# stm_teensy.net
KiCad netlist of a schematic drawn in EAGLE
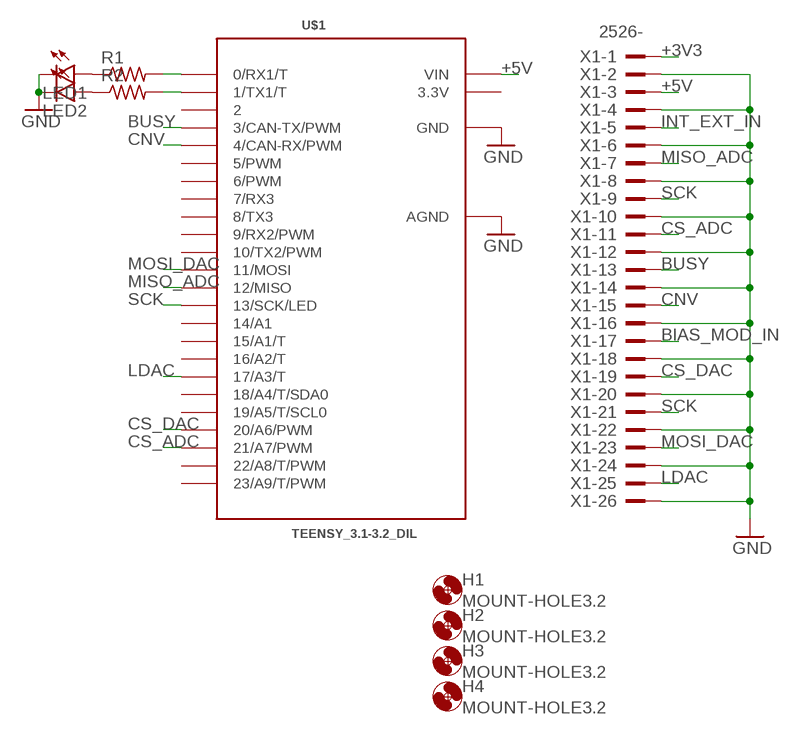
[diagram p0: schematic, sheet 1]

(export (version "E")
  (design (tool "Eeschema 10.0.6"))
  (components
    (comp (ref "H1")
      (value "MOUNT-HOLE3.2")
      (footprint "eagle-import:3,2")
      (libsource (lib "eagle-import") (part "MOUNT-HOLE3.2"))
    )
    (comp (ref "H2")
      (value "MOUNT-HOLE3.2")
      (footprint "eagle-import:3,2")
      (libsource (lib "eagle-import") (part "MOUNT-HOLE3.2"))
    )
    (comp (ref "H3")
      (value "MOUNT-HOLE3.2")
      (footprint "eagle-import:3,2")
      (libsource (lib "eagle-import") (part "MOUNT-HOLE3.2"))
    )
    (comp (ref "H4")
      (value "MOUNT-HOLE3.2")
      (footprint "eagle-import:3,2")
      (libsource (lib "eagle-import") (part "MOUNT-HOLE3.2"))
    )
    (comp (ref "LED1")
      (value "LED5MM")
      (footprint "eagle-import:LED5MM")
      (libsource (lib "eagle-import") (part "LED5MM"))
    )
    (comp (ref "LED2")
      (value "LED5MM")
      (footprint "eagle-import:LED5MM")
      (libsource (lib "eagle-import") (part "LED5MM"))
    )
    (comp (ref "R1")
      (value "R-US_0204/7")
      (footprint "eagle-import:0204_7")
      (libsource (lib "eagle-import") (part "R-US_0204/7"))
    )
    (comp (ref "R2")
      (value "R-US_0204/7")
      (footprint "eagle-import:0204_7")
      (libsource (lib "eagle-import") (part "R-US_0204/7"))
    )
    (comp (ref "U$1")
      (value "TEENSY_3.1-3.2_DIL")
      (footprint "eagle-import:TEENSY_3.0-3.2&LC_DIL")
      (libsource (lib "eagle-import") (part "TEENSY_3.1-3.2_DIL"))
    )
    (comp (ref "X1")
      (value "2526-")
      (footprint "eagle-import:PAK100_2500-26")
      (libsource (lib "eagle-import") (part "2526-"))
    )
  )
  (nets
    (net (code "1") (name "/+3V3") (class "Default")
      (node (ref "X1") (pin "1") (pinfunction "KL_1") (pintype "passive"))
    )
    (net (code "2") (name "/+5V") (class "Default")
      (node (ref "U$1") (pin "VIN") (pinfunction "VIN_VIN") (pintype "power_in"))
      (node (ref "X1") (pin "3") (pinfunction "KL_3") (pintype "passive"))
    )
    (net (code "3") (name "/3.3V") (class "Default")
      (node (ref "U$1") (pin "3.3V") (pinfunction "3.3V_3.3V") (pintype "power_in"))
    )
    (net (code "4") (name "/BIAS_MOD_IN") (class "Default")
      (node (ref "X1") (pin "17") (pinfunction "KL_17") (pintype "passive"))
    )
    (net (code "5") (name "/BUSY") (class "Default")
      (node (ref "U$1") (pin "3") (pinfunction "3/CAN-TX/PWM_3") (pintype "bidirectional"))
      (node (ref "X1") (pin "13") (pinfunction "KL_13") (pintype "passive"))
    )
    (net (code "6") (name "/CNV") (class "Default")
      (node (ref "U$1") (pin "4") (pinfunction "4/CAN-RX/PWM_4") (pintype "bidirectional"))
      (node (ref "X1") (pin "15") (pinfunction "KL_15") (pintype "passive"))
    )
    (net (code "7") (name "/CS_ADC") (class "Default")
      (node (ref "U$1") (pin "21/A7") (pinfunction "21/A7/PWM_21/A7") (pintype "bidirectional"))
      (node (ref "X1") (pin "11") (pinfunction "KL_11") (pintype "passive"))
    )
    (net (code "8") (name "/CS_DAC") (class "Default")
      (node (ref "U$1") (pin "20/A6") (pinfunction "20/A6/PWM_20/A6") (pintype "bidirectional"))
      (node (ref "X1") (pin "19") (pinfunction "KL_19") (pintype "passive"))
    )
    (net (code "9") (name "/INT_EXT_IN") (class "Default")
      (node (ref "X1") (pin "5") (pinfunction "KL_5") (pintype "passive"))
    )
    (net (code "10") (name "/LDAC") (class "Default")
      (node (ref "U$1") (pin "17/A3") (pinfunction "17/A3/T_17/A3") (pintype "bidirectional"))
      (node (ref "X1") (pin "25") (pinfunction "KL_25") (pintype "passive"))
    )
    (net (code "11") (name "/MISO_ADC") (class "Default")
      (node (ref "U$1") (pin "12") (pinfunction "12/MISO_12") (pintype "bidirectional"))
      (node (ref "X1") (pin "7") (pinfunction "KL_7") (pintype "passive"))
    )
    (net (code "12") (name "/MOSI_DAC") (class "Default")
      (node (ref "U$1") (pin "11") (pinfunction "11/MOSI_11") (pintype "bidirectional"))
      (node (ref "X1") (pin "23") (pinfunction "KL_23") (pintype "passive"))
    )
    (net (code "13") (name "/SCK") (class "Default")
      (node (ref "U$1") (pin "13") (pinfunction "13/SCK/LED_13") (pintype "bidirectional"))
      (node (ref "X1") (pin "21") (pinfunction "KL_21") (pintype "passive"))
      (node (ref "X1") (pin "9") (pinfunction "KL_9") (pintype "passive"))
    )
    (net (code "14") (name "GND") (class "Default")
      (node (ref "LED1") (pin "K") (pinfunction "C_K") (pintype "passive"))
      (node (ref "LED2") (pin "K") (pinfunction "C_K") (pintype "passive"))
      (node (ref "U$1") (pin "AGND") (pinfunction "AGND_AGND") (pintype "power_in"))
      (node (ref "U$1") (pin "GND") (pinfunction "GND_GND") (pintype "power_in"))
      (node (ref "X1") (pin "10") (pinfunction "KL_10") (pintype "passive"))
      (node (ref "X1") (pin "12") (pinfunction "KL_12") (pintype "passive"))
      (node (ref "X1") (pin "14") (pinfunction "KL_14") (pintype "passive"))
      (node (ref "X1") (pin "16") (pinfunction "KL_16") (pintype "passive"))
      (node (ref "X1") (pin "18") (pinfunction "KL_18") (pintype "passive"))
      (node (ref "X1") (pin "2") (pinfunction "KL_2") (pintype "passive"))
      (node (ref "X1") (pin "20") (pinfunction "KL_20") (pintype "passive"))
      (node (ref "X1") (pin "22") (pinfunction "KL_22") (pintype "passive"))
      (node (ref "X1") (pin "24") (pinfunction "KL_24") (pintype "passive"))
      (node (ref "X1") (pin "26") (pinfunction "KL_26") (pintype "passive"))
      (node (ref "X1") (pin "4") (pinfunction "KL_4") (pintype "passive"))
      (node (ref "X1") (pin "6") (pinfunction "KL_6") (pintype "passive"))
      (node (ref "X1") (pin "8") (pinfunction "KL_8") (pintype "passive"))
    )
    (net (code "15") (name "Net-(LED1-PadA)") (class "Default")
      (node (ref "LED1") (pin "A") (pinfunction "A_A") (pintype "passive"))
      (node (ref "R1") (pin "1") (pinfunction "1_1") (pintype "passive"))
    )
    (net (code "16") (name "Net-(LED2-PadA)") (class "Default")
      (node (ref "LED2") (pin "A") (pinfunction "A_A") (pintype "passive"))
      (node (ref "R2") (pin "1") (pinfunction "1_1") (pintype "passive"))
    )
    (net (code "17") (name "Net-(U$1-0{slash}RX1{slash}T)") (class "Default")
      (node (ref "R1") (pin "2") (pinfunction "2_2") (pintype "passive"))
      (node (ref "U$1") (pin "0") (pinfunction "0/RX1/T_0") (pintype "bidirectional"))
    )
    (net (code "18") (name "Net-(U$1-1{slash}TX1{slash}T)") (class "Default")
      (node (ref "R2") (pin "2") (pinfunction "2_2") (pintype "passive"))
      (node (ref "U$1") (pin "1") (pinfunction "1/TX1/T_1") (pintype "bidirectional"))
    )
    (net (code "19") (name "unconnected-(U$1-5{slash}PWM-Pad5)") (class "Default")
      (node (ref "U$1") (pin "5") (pinfunction "5/PWM_5") (pintype "bidirectional"))
    )
    (net (code "20") (name "unconnected-(U$1-6{slash}PWM-Pad6)") (class "Default")
      (node (ref "U$1") (pin "6") (pinfunction "6/PWM_6") (pintype "bidirectional"))
    )
    (net (code "21") (name "unconnected-(U$1-7{slash}RX3-Pad7)") (class "Default")
      (node (ref "U$1") (pin "7") (pinfunction "7/RX3_7") (pintype "bidirectional"))
    )
    (net (code "22") (name "unconnected-(U$1-8{slash}TX3-Pad8)") (class "Default")
      (node (ref "U$1") (pin "8") (pinfunction "8/TX3_8") (pintype "bidirectional"))
    )
    (net (code "23") (name "unconnected-(U$1-9{slash}RX2{slash}PWM-Pad9)") (class "Default")
      (node (ref "U$1") (pin "9") (pinfunction "9/RX2/PWM_9") (pintype "bidirectional"))
    )
    (net (code "24") (name "unconnected-(U$1-10{slash}TX2{slash}PWM-Pad10)") (class "Default")
      (node (ref "U$1") (pin "10") (pinfunction "10/TX2/PWM_10") (pintype "bidirectional"))
    )
    (net (code "25") (name "unconnected-(U$1-14{slash}A1-Pad14{slash}A0)") (class "Default")
      (node (ref "U$1") (pin "14/A0") (pinfunction "14/A1_14/A0") (pintype "bidirectional"))
    )
    (net (code "26") (name "unconnected-(U$1-15{slash}A1{slash}T-Pad15{slash}A1)") (class "Default")
      (node (ref "U$1") (pin "15/A1") (pinfunction "15/A1/T_15/A1") (pintype "bidirectional"))
    )
    (net (code "27") (name "unconnected-(U$1-16{slash}A2{slash}T-Pad16{slash}A2)") (class "Default")
      (node (ref "U$1") (pin "16/A2") (pinfunction "16/A2/T_16/A2") (pintype "bidirectional"))
    )
    (net (code "28") (name "unconnected-(U$1-18{slash}A4{slash}T{slash}SDA0-Pad18{slash}A4)") (class "Default")
      (node (ref "U$1") (pin "18/A4") (pinfunction "18/A4/T/SDA0_18/A4") (pintype "bidirectional"))
    )
    (net (code "29") (name "unconnected-(U$1-19{slash}A5{slash}T{slash}SCL0-Pad19{slash}A5)") (class "Default")
      (node (ref "U$1") (pin "19/A5") (pinfunction "19/A5/T/SCL0_19/A5") (pintype "bidirectional"))
    )
    (net (code "30") (name "unconnected-(U$1-22{slash}A8{slash}T{slash}PWM-Pad22{slash}A8)") (class "Default")
      (node (ref "U$1") (pin "22/A8") (pinfunction "22/A8/T/PWM_22/A8") (pintype "bidirectional"))
    )
    (net (code "31") (name "unconnected-(U$1-23{slash}A9{slash}T{slash}PWM-Pad23{slash}A9)") (class "Default")
      (node (ref "U$1") (pin "23/A9") (pinfunction "23/A9/T/PWM_23/A9") (pintype "bidirectional"))
    )
    (net (code "32") (name "unconnected-(U$1-Pad2)") (class "Default")
      (node (ref "U$1") (pin "2") (pinfunction "2_2") (pintype "bidirectional"))
    )
  )
)
